# Reciever.net
KiCad netlist of a schematic drawn in Altium Designer
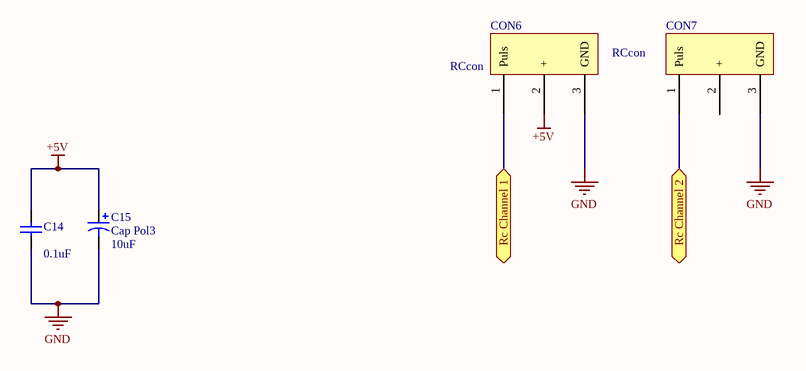
[diagram p0: Reciever.SchDoc]

(export (version "E")
  (design (tool "Eeschema 10.0.6"))
  (components
    (comp (ref "C14")
      (value "0.1uF")
      (footprint "C1206")
      (description "Capacitor (Semiconductor SIM Model)")
      (fields (field (name "Comment") "Cap Semi") (field (name "PUBLISHER") "Altium Limited"))
      (libsource (lib "Miscellaneous Devices") (part "Cap Semi"))
    )
    (comp (ref "C15")
      (value "Cap Pol3")
      (footprint "C0805")
      (description "Polarized Capacitor (Surface Mount)")
      (fields (field (name "ALTIUM_VALUE") "10uF") (field (name "PUBLISHER") "Altium Limited"))
      (libsource (lib "Miscellaneous Devices") (part "Cap Pol3"))
    )
    (comp (ref "CON6") (value "RCcon") (footprint "RcCon") (libsource (lib "RcCon") (part "Rc con")))
    (comp (ref "CON7") (value "RCcon") (footprint "RcCon") (libsource (lib "RcCon") (part "Rc con")))
  )
  (nets
    (net (code "1") (name "+5V") (class "Default")
      (node (ref "C14") (pin "1") (pinfunction "1_1") (pintype "passive"))
      (node (ref "C15") (pin "1") (pinfunction "1_1") (pintype "passive"))
      (node (ref "CON6") (pin "2") (pinfunction "+_2") (pintype "passive"))
    )
    (net (code "2") (name "/Rc Channel 1") (class "Default")
      (node (ref "CON6") (pin "1") (pinfunction "Puls_1") (pintype "passive"))
    )
    (net (code "3") (name "/Rc Channel 2") (class "Default")
      (node (ref "CON7") (pin "1") (pinfunction "Puls_1") (pintype "passive"))
    )
    (net (code "4") (name "GND") (class "Default")
      (node (ref "C14") (pin "2") (pinfunction "2_2") (pintype "passive"))
      (node (ref "C15") (pin "2") (pinfunction "2_2") (pintype "passive"))
      (node (ref "CON6") (pin "3") (pinfunction "GND_3") (pintype "passive"))
      (node (ref "CON7") (pin "3") (pinfunction "GND_3") (pintype "passive"))
    )
    (net (code "5") (name "unconnected-(CON7-+-Pad2)") (class "Default")
      (node (ref "CON7") (pin "2") (pinfunction "+_2") (pintype "passive"))
    )
  )
)
